# Papierski_Dice_3.net
KiCad netlist of a schematic drawn in EAGLE
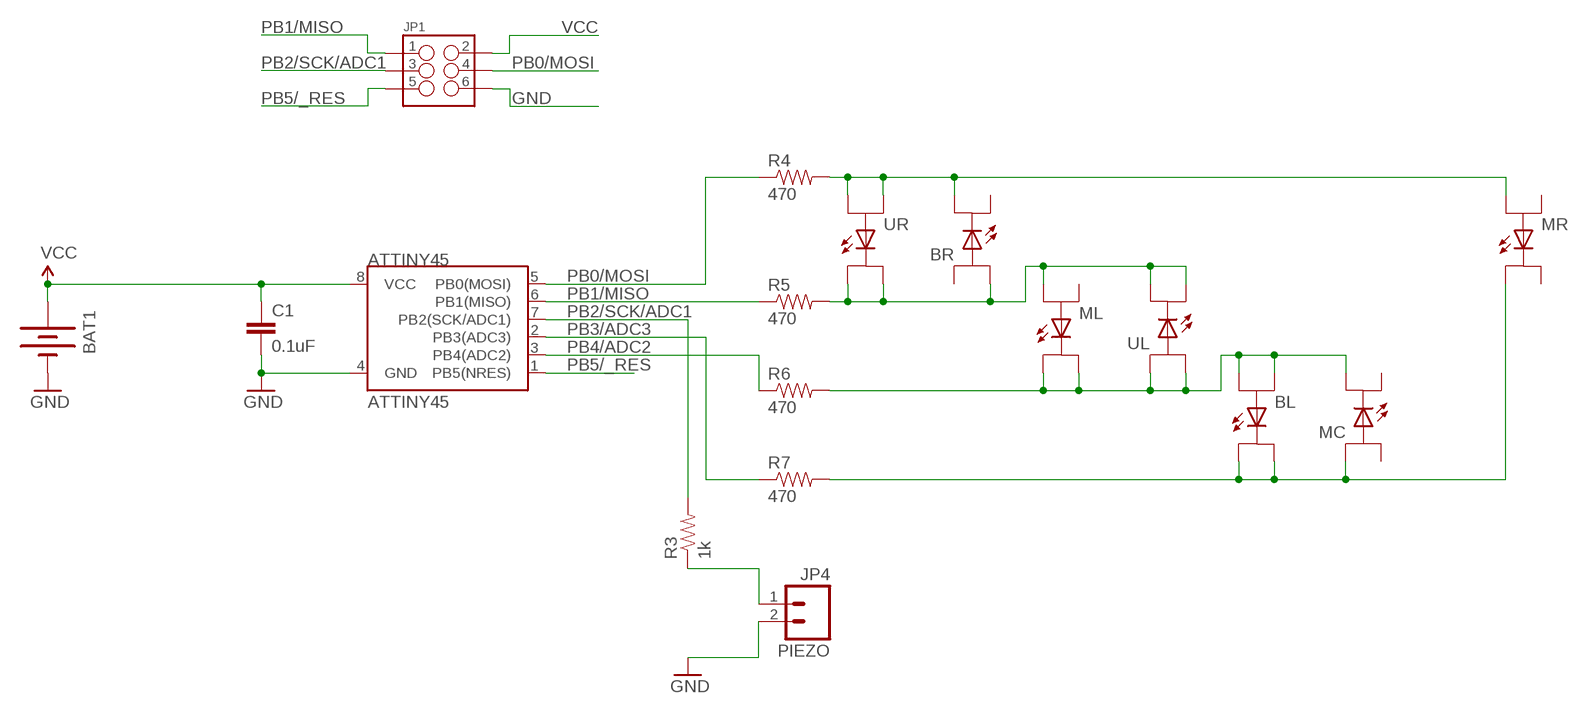
[diagram p0: schematic, sheet 1]

(export (version "E")
  (design (tool "Eeschema 10.0.6"))
  (components
    (comp (ref "ATTINY45")
      (value "ATTINY45")
      (footprint "eagle-import:SO08-EIAJ")
      (libsource (lib "eagle-import") (part "ATTINY45TINY85-20-SMT"))
    )
    (comp (ref "BAT1")
      (value "BATTERY20PTH")
      (footprint "eagle-import:BATTCOM_20MM_PTH")
      (libsource (lib "eagle-import") (part "BATTERY20PTH"))
    )
    (comp (ref "BL")
      (value "LED_PIRANHA_5MM_SNGLS")
      (footprint "eagle-import:LED_PIRANHA_5MM_SNGL_SMD")
      (libsource (lib "eagle-import") (part "LED_PIRANHA_5MM_SNGLS"))
    )
    (comp (ref "BR")
      (value "LED_PIRANHA_5MM_SNGLS")
      (footprint "eagle-import:LED_PIRANHA_5MM_SNGL_SMD")
      (libsource (lib "eagle-import") (part "LED_PIRANHA_5MM_SNGLS"))
    )
    (comp (ref "C1")
      (value "0.1uF")
      (footprint "eagle-import:0805")
      (libsource (lib "eagle-import") (part "CAP0805"))
    )
    (comp (ref "JP1")
      (value "M03X2NO_SILK")
      (footprint "eagle-import:2X3-NS")
      (libsource (lib "eagle-import") (part "M03X2NO_SILK"))
    )
    (comp (ref "MC")
      (value "LED_PIRANHA_5MM_SNGLS")
      (footprint "eagle-import:LED_PIRANHA_5MM_SNGL_SMD")
      (libsource (lib "eagle-import") (part "LED_PIRANHA_5MM_SNGLS"))
    )
    (comp (ref "ML")
      (value "LED_PIRANHA_5MM_SNGLS")
      (footprint "eagle-import:LED_PIRANHA_5MM_SNGL_SMD")
      (libsource (lib "eagle-import") (part "LED_PIRANHA_5MM_SNGLS"))
    )
    (comp (ref "MR")
      (value "LED_PIRANHA_5MM_SNGLS")
      (footprint "eagle-import:LED_PIRANHA_5MM_SNGL_SMD")
      (libsource (lib "eagle-import") (part "LED_PIRANHA_5MM_SNGLS"))
    )
    (comp (ref "PIEZO")
      (value "JP4")
      (footprint "eagle-import:1X02")
      (libsource (lib "eagle-import") (part "M02PTH"))
    )
    (comp (ref "R3")
      (value "1k")
      (footprint "eagle-import:AXIAL-0.3")
      (libsource (lib "eagle-import") (part "RESISTORAXIAL-0.3"))
    )
    (comp (ref "R4")
      (value "470")
      (footprint "eagle-import:AXIAL-0.3")
      (libsource (lib "eagle-import") (part "RESISTORAXIAL-0.3"))
    )
    (comp (ref "R5")
      (value "470")
      (footprint "eagle-import:AXIAL-0.3")
      (libsource (lib "eagle-import") (part "RESISTORAXIAL-0.3"))
    )
    (comp (ref "R6")
      (value "470")
      (footprint "eagle-import:AXIAL-0.3")
      (libsource (lib "eagle-import") (part "RESISTORAXIAL-0.3"))
    )
    (comp (ref "R7")
      (value "470")
      (footprint "eagle-import:0805")
      (libsource (lib "eagle-import") (part "RESISTOR0805-RES"))
    )
    (comp (ref "UL")
      (value "LED_PIRANHA_5MM_SNGLS")
      (footprint "eagle-import:LED_PIRANHA_5MM_SNGL_SMD")
      (libsource (lib "eagle-import") (part "LED_PIRANHA_5MM_SNGLS"))
    )
    (comp (ref "UR")
      (value "LED_PIRANHA_5MM_SNGLS")
      (footprint "eagle-import:LED_PIRANHA_5MM_SNGL_SMD")
      (libsource (lib "eagle-import") (part "LED_PIRANHA_5MM_SNGLS"))
    )
  )
  (nets
    (net (code "1") (name "/PB0{slash}MOSI") (class "Default")
      (node (ref "ATTINY45") (pin "5") (pinfunction "PB0(MOSI)_5") (pintype "bidirectional"))
      (node (ref "JP1") (pin "4") (pinfunction "4_4") (pintype "bidirectional"))
      (node (ref "R4") (pin "P$1") (pinfunction "1_P$1") (pintype "passive"))
    )
    (net (code "2") (name "/PB1{slash}MISO") (class "Default")
      (node (ref "ATTINY45") (pin "6") (pinfunction "PB1(MISO)_6") (pintype "bidirectional"))
      (node (ref "JP1") (pin "1") (pinfunction "1_1") (pintype "bidirectional"))
      (node (ref "R5") (pin "P$1") (pinfunction "1_P$1") (pintype "passive"))
    )
    (net (code "3") (name "/PB2{slash}SCK{slash}ADC1") (class "Default")
      (node (ref "ATTINY45") (pin "7") (pinfunction "PB2(SCK/ADC1)_7") (pintype "bidirectional"))
      (node (ref "JP1") (pin "3") (pinfunction "3_3") (pintype "bidirectional"))
      (node (ref "R3") (pin "P$2") (pinfunction "2_P$2") (pintype "passive"))
    )
    (net (code "4") (name "/PB3{slash}ADC3") (class "Default")
      (node (ref "ATTINY45") (pin "2") (pinfunction "PB3(ADC3)_2") (pintype "bidirectional"))
      (node (ref "R7") (pin "1") (pinfunction "1_1") (pintype "passive"))
    )
    (net (code "5") (name "/PB4{slash}ADC2") (class "Default")
      (node (ref "ATTINY45") (pin "3") (pinfunction "PB4(ADC2)_3") (pintype "bidirectional"))
      (node (ref "R6") (pin "P$1") (pinfunction "1_P$1") (pintype "passive"))
    )
    (net (code "6") (name "/PB5{slash}_RES") (class "Default")
      (node (ref "ATTINY45") (pin "1") (pinfunction "PB5(NRES)_1") (pintype "bidirectional"))
      (node (ref "JP1") (pin "5") (pinfunction "5_5") (pintype "bidirectional"))
    )
    (net (code "7") (name "GND") (class "Default")
      (node (ref "ATTINY45") (pin "4") (pinfunction "GND_4") (pintype "bidirectional"))
      (node (ref "BAT1") (pin "2") (pinfunction "-_2") (pintype "power_in"))
      (node (ref "C1") (pin "2") (pinfunction "2_2") (pintype "passive"))
      (node (ref "JP1") (pin "6") (pinfunction "6_6") (pintype "bidirectional"))
      (node (ref "PIEZO") (pin "2") (pinfunction "2_2") (pintype "passive"))
    )
    (net (code "8") (name "Net-(BL-C1)") (class "Default")
      (node (ref "BL") (pin "K1") (pinfunction "C1_K1") (pintype "passive"))
      (node (ref "BL") (pin "K2") (pinfunction "C2_K2") (pintype "passive"))
      (node (ref "MC") (pin "A2") (pinfunction "A2_A2") (pintype "passive"))
      (node (ref "MR") (pin "K2") (pinfunction "C2_K2") (pintype "passive"))
      (node (ref "R7") (pin "2") (pinfunction "2_2") (pintype "passive"))
    )
    (net (code "9") (name "Net-(BR-C1)") (class "Default")
      (node (ref "BR") (pin "K1") (pinfunction "C1_K1") (pintype "passive"))
      (node (ref "MR") (pin "A1") (pinfunction "A1_A1") (pintype "passive"))
      (node (ref "R4") (pin "P$2") (pinfunction "2_P$2") (pintype "passive"))
      (node (ref "UR") (pin "A1") (pinfunction "A1_A1") (pintype "passive"))
      (node (ref "UR") (pin "A2") (pinfunction "A2_A2") (pintype "passive"))
    )
    (net (code "10") (name "Net-(MC-C1)") (class "Default")
      (node (ref "BL") (pin "A1") (pinfunction "A1_A1") (pintype "passive"))
      (node (ref "BL") (pin "A2") (pinfunction "A2_A2") (pintype "passive"))
      (node (ref "MC") (pin "K1") (pinfunction "C1_K1") (pintype "passive"))
      (node (ref "ML") (pin "K1") (pinfunction "C1_K1") (pintype "passive"))
      (node (ref "ML") (pin "K2") (pinfunction "C2_K2") (pintype "passive"))
      (node (ref "R6") (pin "P$2") (pinfunction "2_P$2") (pintype "passive"))
      (node (ref "UL") (pin "A1") (pinfunction "A1_A1") (pintype "passive"))
      (node (ref "UL") (pin "A2") (pinfunction "A2_A2") (pintype "passive"))
    )
    (net (code "11") (name "Net-(R3-1)") (class "Default")
      (node (ref "PIEZO") (pin "1") (pinfunction "1_1") (pintype "passive"))
      (node (ref "R3") (pin "P$1") (pinfunction "1_P$1") (pintype "passive"))
    )
    (net (code "12") (name "Net-(R5-2)") (class "Default")
      (node (ref "BR") (pin "A1") (pinfunction "A1_A1") (pintype "passive"))
      (node (ref "ML") (pin "A1") (pinfunction "A1_A1") (pintype "passive"))
      (node (ref "R5") (pin "P$2") (pinfunction "2_P$2") (pintype "passive"))
      (node (ref "UL") (pin "K1") (pinfunction "C1_K1") (pintype "passive"))
      (node (ref "UL") (pin "K2") (pinfunction "C2_K2") (pintype "passive"))
      (node (ref "UR") (pin "K1") (pinfunction "C1_K1") (pintype "passive"))
      (node (ref "UR") (pin "K2") (pinfunction "C2_K2") (pintype "passive"))
    )
    (net (code "13") (name "VCC") (class "Default")
      (node (ref "ATTINY45") (pin "8") (pinfunction "VCC_8") (pintype "bidirectional"))
      (node (ref "BAT1") (pin "1") (pinfunction "+_1") (pintype "power_in"))
      (node (ref "C1") (pin "1") (pinfunction "1_1") (pintype "passive"))
      (node (ref "JP1") (pin "2") (pinfunction "2_2") (pintype "bidirectional"))
    )
    (net (code "14") (name "unconnected-(BR-C2-PadK2)") (class "Default")
      (node (ref "BR") (pin "K2") (pinfunction "C2_K2") (pintype "passive"))
    )
    (net (code "15") (name "unconnected-(BR-PadA2)") (class "Default")
      (node (ref "BR") (pin "A2") (pinfunction "A2_A2") (pintype "passive"))
    )
    (net (code "16") (name "unconnected-(MC-C2-PadK2)") (class "Default")
      (node (ref "MC") (pin "K2") (pinfunction "C2_K2") (pintype "passive"))
    )
    (net (code "17") (name "unconnected-(MC-PadA1)") (class "Default")
      (node (ref "MC") (pin "A1") (pinfunction "A1_A1") (pintype "passive"))
    )
    (net (code "18") (name "unconnected-(ML-PadA2)") (class "Default")
      (node (ref "ML") (pin "A2") (pinfunction "A2_A2") (pintype "passive"))
    )
    (net (code "19") (name "unconnected-(MR-C1-PadK1)") (class "Default")
      (node (ref "MR") (pin "K1") (pinfunction "C1_K1") (pintype "passive"))
    )
    (net (code "20") (name "unconnected-(MR-PadA2)") (class "Default")
      (node (ref "MR") (pin "A2") (pinfunction "A2_A2") (pintype "passive"))
    )
  )
)
